# board1_328.net
KiCad netlist of a schematic drawn in EAGLE
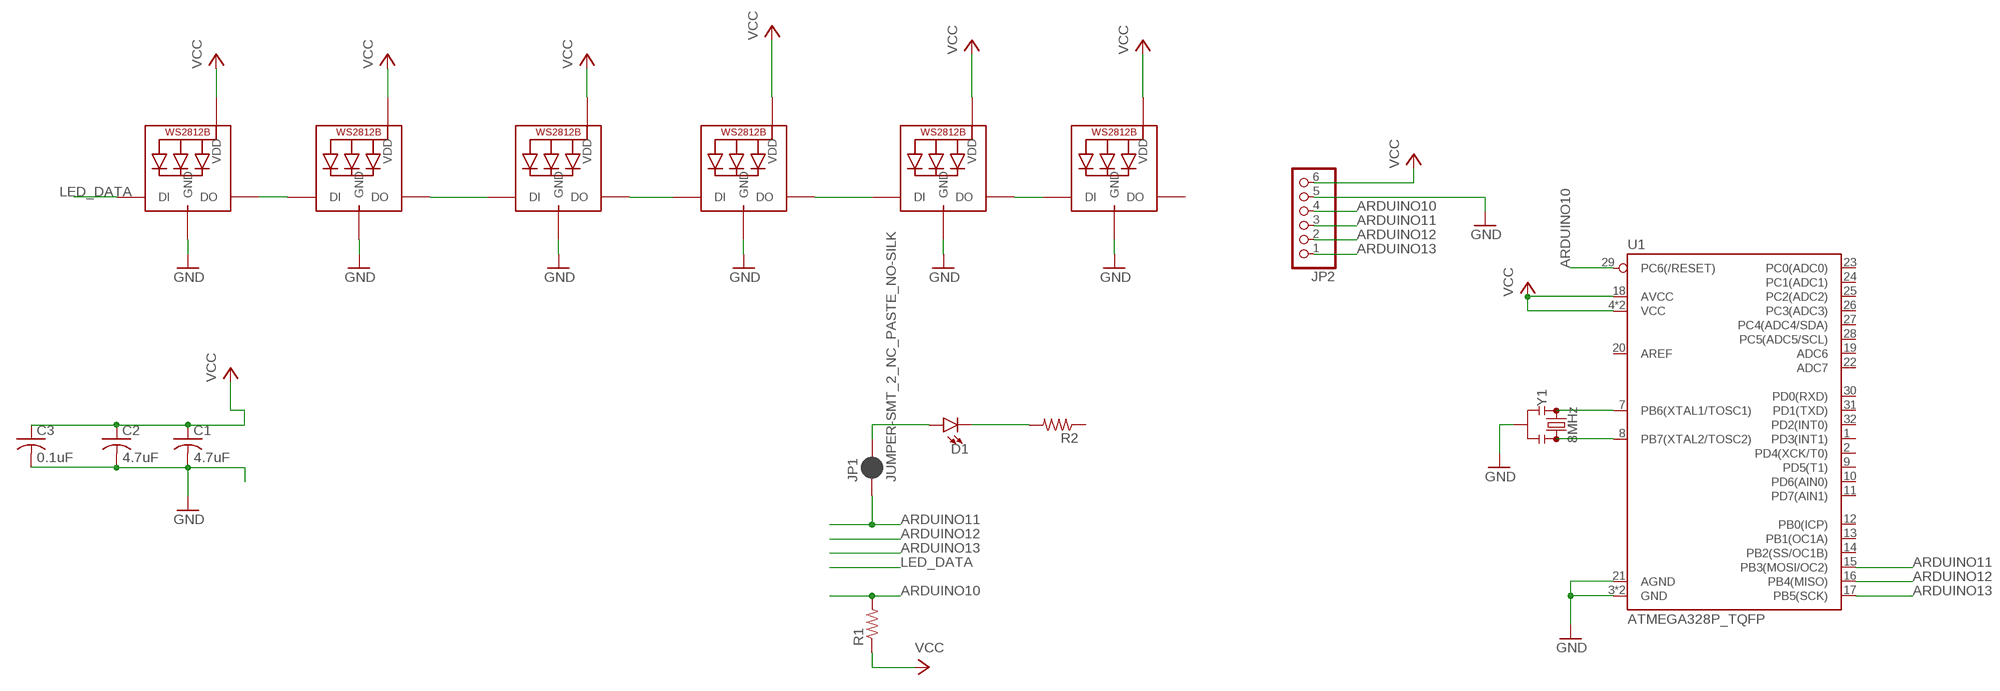
[diagram p0: schematic, sheet 1]

(export (version "E")
  (design (tool "Eeschema 10.0.6"))
  (components
    (comp (ref "C1")
      (value "4.7uF")
      (footprint "eagle-import:C0603")
      (libsource (lib "eagle-import") (part "C-USC0603"))
    )
    (comp (ref "C2")
      (value "4.7uF")
      (footprint "eagle-import:C0603")
      (libsource (lib "eagle-import") (part "C-USC0603"))
    )
    (comp (ref "C3")
      (value "0.1uF")
      (footprint "eagle-import:C0603")
      (libsource (lib "eagle-import") (part "C-USC0603"))
    )
    (comp (ref "D1")
      (value "LED0603")
      (footprint "eagle-import:LED-0603")
      (libsource (lib "eagle-import") (part "LED0603"))
    )
    (comp (ref "JP1")
      (value "JUMPER-SMT_2_NC_PASTE_NO-SILK")
      (footprint "eagle-import:SMT-JUMPER_2_NC_PASTE_NO-SILK")
      (libsource (lib "eagle-import") (part "JUMPER-SMT_2_NC_PASTE_NO-SILK"))
    )
    (comp (ref "JP2")
      (value "PINHD-1X6")
      (footprint "eagle-import:1X06")
      (libsource (lib "eagle-import") (part "PINHD-1X6"))
    )
    (comp (ref "LED1")
      (value "WS2812B5050")
      (footprint "eagle-import:WS2812B")
      (libsource (lib "eagle-import") (part "WS2812B5050"))
    )
    (comp (ref "LED2")
      (value "WS2812B5050")
      (footprint "eagle-import:WS2812B")
      (libsource (lib "eagle-import") (part "WS2812B5050"))
    )
    (comp (ref "LED3")
      (value "WS2812B5050")
      (footprint "eagle-import:WS2812B")
      (libsource (lib "eagle-import") (part "WS2812B5050"))
    )
    (comp (ref "LED4")
      (value "WS2812B5050")
      (footprint "eagle-import:WS2812B")
      (libsource (lib "eagle-import") (part "WS2812B5050"))
    )
    (comp (ref "LED5")
      (value "WS2812B5050")
      (footprint "eagle-import:WS2812B")
      (libsource (lib "eagle-import") (part "WS2812B5050"))
    )
    (comp (ref "LED6")
      (value "WS2812B5050")
      (footprint "eagle-import:WS2812B")
      (libsource (lib "eagle-import") (part "WS2812B5050"))
    )
    (comp (ref "R1")
      (value "R-US_R0603")
      (footprint "eagle-import:R0603")
      (libsource (lib "eagle-import") (part "R-US_R0603"))
    )
    (comp (ref "R2")
      (value "R-US_R0603")
      (footprint "eagle-import:R0603")
      (libsource (lib "eagle-import") (part "R-US_R0603"))
    )
    (comp (ref "U1")
      (value "ATMEGA328P_TQFP")
      (footprint "eagle-import:TQFP32-08")
      (libsource (lib "eagle-import") (part "ATMEGA328P_TQFP"))
    )
    (comp (ref "Y1")
      (value "8MHz")
      (footprint "eagle-import:RESONATOR-SMD-3.2X1.3")
      (libsource (lib "eagle-import") (part "RESONATOR-8MHZSMD_3.2X1.3"))
    )
  )
  (nets
    (net (code "1") (name "/ARDUINO10") (class "Default")
      (node (ref "JP2") (pin "4") (pinfunction "4_4") (pintype "passive"))
      (node (ref "R1") (pin "2") (pinfunction "2_2") (pintype "passive"))
      (node (ref "U1") (pin "29") (pinfunction "PC6(/RESET)_29") (pintype "bidirectional"))
    )
    (net (code "2") (name "/ARDUINO11") (class "Default")
      (node (ref "JP1") (pin "1") (pinfunction "1_1") (pintype "passive"))
      (node (ref "JP2") (pin "3") (pinfunction "3_3") (pintype "passive"))
      (node (ref "U1") (pin "15") (pinfunction "PB3(MOSI/OC2)_15") (pintype "bidirectional"))
    )
    (net (code "3") (name "/ARDUINO12") (class "Default")
      (node (ref "JP2") (pin "2") (pinfunction "2_2") (pintype "passive"))
      (node (ref "U1") (pin "16") (pinfunction "PB4(MISO)_16") (pintype "bidirectional"))
    )
    (net (code "4") (name "/ARDUINO13") (class "Default")
      (node (ref "JP2") (pin "1") (pinfunction "1_1") (pintype "passive"))
      (node (ref "U1") (pin "17") (pinfunction "PB5(SCK)_17") (pintype "bidirectional"))
    )
    (net (code "5") (name "/LED_DATA") (class "Default")
      (node (ref "LED1") (pin "4-DIN") (pinfunction "DI_4-DIN") (pintype "input"))
    )
    (net (code "6") (name "GND") (class "Default")
      (node (ref "C1") (pin "2") (pinfunction "2_2") (pintype "passive"))
      (node (ref "C2") (pin "2") (pinfunction "2_2") (pintype "passive"))
      (node (ref "C3") (pin "2") (pinfunction "2_2") (pintype "passive"))
      (node (ref "JP2") (pin "5") (pinfunction "5_5") (pintype "passive"))
      (node (ref "LED1") (pin "3-GND") (pinfunction "GND_3-GND") (pintype "power_in"))
      (node (ref "LED2") (pin "3-GND") (pinfunction "GND_3-GND") (pintype "power_in"))
      (node (ref "LED3") (pin "3-GND") (pinfunction "GND_3-GND") (pintype "power_in"))
      (node (ref "LED4") (pin "3-GND") (pinfunction "GND_3-GND") (pintype "power_in"))
      (node (ref "LED5") (pin "3-GND") (pinfunction "GND_3-GND") (pintype "power_in"))
      (node (ref "LED6") (pin "3-GND") (pinfunction "GND_3-GND") (pintype "power_in"))
      (node (ref "U1") (pin "21") (pinfunction "AGND_21") (pintype "bidirectional"))
      (node (ref "U1") (pin "3") (pinfunction "GND_3") (pintype "bidirectional"))
      (node (ref "U1") (pin "5") (pinfunction "GND_5") (pintype "bidirectional"))
      (node (ref "Y1") (pin "2") (pinfunction "2_2") (pintype "passive"))
    )
    (net (code "7") (name "Net-(D1-PadA)") (class "Default")
      (node (ref "D1") (pin "A") (pinfunction "A_A") (pintype "passive"))
      (node (ref "JP1") (pin "2") (pinfunction "2_2") (pintype "passive"))
    )
    (net (code "8") (name "Net-(D1-PadC)") (class "Default")
      (node (ref "D1") (pin "C") (pinfunction "C_C") (pintype "passive"))
      (node (ref "R2") (pin "2") (pinfunction "2_2") (pintype "passive"))
    )
    (net (code "9") (name "Net-(LED1-DO)") (class "Default")
      (node (ref "LED1") (pin "2-DOUT") (pinfunction "DO_2-DOUT") (pintype "output"))
      (node (ref "LED2") (pin "4-DIN") (pinfunction "DI_4-DIN") (pintype "input"))
    )
    (net (code "10") (name "Net-(LED2-DO)") (class "Default")
      (node (ref "LED2") (pin "2-DOUT") (pinfunction "DO_2-DOUT") (pintype "output"))
      (node (ref "LED3") (pin "4-DIN") (pinfunction "DI_4-DIN") (pintype "input"))
    )
    (net (code "11") (name "Net-(LED3-DO)") (class "Default")
      (node (ref "LED3") (pin "2-DOUT") (pinfunction "DO_2-DOUT") (pintype "output"))
      (node (ref "LED4") (pin "4-DIN") (pinfunction "DI_4-DIN") (pintype "input"))
    )
    (net (code "12") (name "Net-(LED4-DO)") (class "Default")
      (node (ref "LED4") (pin "2-DOUT") (pinfunction "DO_2-DOUT") (pintype "output"))
      (node (ref "LED5") (pin "4-DIN") (pinfunction "DI_4-DIN") (pintype "input"))
    )
    (net (code "13") (name "Net-(LED5-DO)") (class "Default")
      (node (ref "LED5") (pin "2-DOUT") (pinfunction "DO_2-DOUT") (pintype "output"))
      (node (ref "LED6") (pin "4-DIN") (pinfunction "DI_4-DIN") (pintype "input"))
    )
    (net (code "14") (name "Net-(U1-PB6(XTAL1{slash}TOSC1))") (class "Default")
      (node (ref "U1") (pin "7") (pinfunction "PB6(XTAL1/TOSC1)_7") (pintype "bidirectional"))
      (node (ref "Y1") (pin "1") (pinfunction "1_1") (pintype "passive"))
    )
    (net (code "15") (name "Net-(U1-PB7(XTAL2{slash}TOSC2))") (class "Default")
      (node (ref "U1") (pin "8") (pinfunction "PB7(XTAL2/TOSC2)_8") (pintype "bidirectional"))
      (node (ref "Y1") (pin "3") (pinfunction "3_3") (pintype "passive"))
    )
    (net (code "16") (name "VCC") (class "Default")
      (node (ref "C1") (pin "1") (pinfunction "1_1") (pintype "passive"))
      (node (ref "C2") (pin "1") (pinfunction "1_1") (pintype "passive"))
      (node (ref "C3") (pin "1") (pinfunction "1_1") (pintype "passive"))
      (node (ref "JP2") (pin "6") (pinfunction "6_6") (pintype "passive"))
      (node (ref "LED1") (pin "1-VDD") (pinfunction "VDD_1-VDD") (pintype "power_in"))
      (node (ref "LED2") (pin "1-VDD") (pinfunction "VDD_1-VDD") (pintype "power_in"))
      (node (ref "LED3") (pin "1-VDD") (pinfunction "VDD_1-VDD") (pintype "power_in"))
      (node (ref "LED4") (pin "1-VDD") (pinfunction "VDD_1-VDD") (pintype "power_in"))
      (node (ref "LED5") (pin "1-VDD") (pinfunction "VDD_1-VDD") (pintype "power_in"))
      (node (ref "LED6") (pin "1-VDD") (pinfunction "VDD_1-VDD") (pintype "power_in"))
      (node (ref "R1") (pin "1") (pinfunction "1_1") (pintype "passive"))
      (node (ref "U1") (pin "18") (pinfunction "AVCC_18") (pintype "bidirectional"))
      (node (ref "U1") (pin "4") (pinfunction "VCC_4") (pintype "bidirectional"))
      (node (ref "U1") (pin "6") (pinfunction "VCC_6") (pintype "bidirectional"))
    )
    (net (code "17") (name "unconnected-(LED6-DO-Pad2-DOUT)") (class "Default")
      (node (ref "LED6") (pin "2-DOUT") (pinfunction "DO_2-DOUT") (pintype "output"))
    )
    (net (code "18") (name "unconnected-(R2-Pad1)") (class "Default")
      (node (ref "R2") (pin "1") (pinfunction "1_1") (pintype "passive"))
    )
    (net (code "19") (name "unconnected-(U1-ADC6-Pad19)") (class "Default")
      (node (ref "U1") (pin "19") (pinfunction "ADC6_19") (pintype "bidirectional"))
    )
    (net (code "20") (name "unconnected-(U1-ADC7-Pad22)") (class "Default")
      (node (ref "U1") (pin "22") (pinfunction "ADC7_22") (pintype "bidirectional"))
    )
    (net (code "21") (name "unconnected-(U1-AREF-Pad20)") (class "Default")
      (node (ref "U1") (pin "20") (pinfunction "AREF_20") (pintype "bidirectional"))
    )
    (net (code "22") (name "unconnected-(U1-PB0(ICP)-Pad12)") (class "Default")
      (node (ref "U1") (pin "12") (pinfunction "PB0(ICP)_12") (pintype "bidirectional"))
    )
    (net (code "23") (name "unconnected-(U1-PB1(OC1A)-Pad13)") (class "Default")
      (node (ref "U1") (pin "13") (pinfunction "PB1(OC1A)_13") (pintype "bidirectional"))
    )
    (net (code "24") (name "unconnected-(U1-PB2(SS{slash}OC1B)-Pad14)") (class "Default")
      (node (ref "U1") (pin "14") (pinfunction "PB2(SS/OC1B)_14") (pintype "bidirectional"))
    )
    (net (code "25") (name "unconnected-(U1-PC0(ADC0)-Pad23)") (class "Default")
      (node (ref "U1") (pin "23") (pinfunction "PC0(ADC0)_23") (pintype "bidirectional"))
    )
    (net (code "26") (name "unconnected-(U1-PC1(ADC1)-Pad24)") (class "Default")
      (node (ref "U1") (pin "24") (pinfunction "PC1(ADC1)_24") (pintype "bidirectional"))
    )
    (net (code "27") (name "unconnected-(U1-PC2(ADC2)-Pad25)") (class "Default")
      (node (ref "U1") (pin "25") (pinfunction "PC2(ADC2)_25") (pintype "bidirectional"))
    )
    (net (code "28") (name "unconnected-(U1-PC3(ADC3)-Pad26)") (class "Default")
      (node (ref "U1") (pin "26") (pinfunction "PC3(ADC3)_26") (pintype "bidirectional"))
    )
    (net (code "29") (name "unconnected-(U1-PC4(ADC4{slash}SDA)-Pad27)") (class "Default")
      (node (ref "U1") (pin "27") (pinfunction "PC4(ADC4/SDA)_27") (pintype "bidirectional"))
    )
    (net (code "30") (name "unconnected-(U1-PC5(ADC5{slash}SCL)-Pad28)") (class "Default")
      (node (ref "U1") (pin "28") (pinfunction "PC5(ADC5/SCL)_28") (pintype "bidirectional"))
    )
    (net (code "31") (name "unconnected-(U1-PD0(RXD)-Pad30)") (class "Default")
      (node (ref "U1") (pin "30") (pinfunction "PD0(RXD)_30") (pintype "bidirectional"))
    )
    (net (code "32") (name "unconnected-(U1-PD1(TXD)-Pad31)") (class "Default")
      (node (ref "U1") (pin "31") (pinfunction "PD1(TXD)_31") (pintype "bidirectional"))
    )
    (net (code "33") (name "unconnected-(U1-PD2(INT0)-Pad32)") (class "Default")
      (node (ref "U1") (pin "32") (pinfunction "PD2(INT0)_32") (pintype "bidirectional"))
    )
    (net (code "34") (name "unconnected-(U1-PD3(INT1)-Pad1)") (class "Default")
      (node (ref "U1") (pin "1") (pinfunction "PD3(INT1)_1") (pintype "bidirectional"))
    )
    (net (code "35") (name "unconnected-(U1-PD4(XCK{slash}T0)-Pad2)") (class "Default")
      (node (ref "U1") (pin "2") (pinfunction "PD4(XCK/T0)_2") (pintype "bidirectional"))
    )
    (net (code "36") (name "unconnected-(U1-PD5(T1)-Pad9)") (class "Default")
      (node (ref "U1") (pin "9") (pinfunction "PD5(T1)_9") (pintype "bidirectional"))
    )
    (net (code "37") (name "unconnected-(U1-PD6(AIN0)-Pad10)") (class "Default")
      (node (ref "U1") (pin "10") (pinfunction "PD6(AIN0)_10") (pintype "bidirectional"))
    )
    (net (code "38") (name "unconnected-(U1-PD7(AIN1)-Pad11)") (class "Default")
      (node (ref "U1") (pin "11") (pinfunction "PD7(AIN1)_11") (pintype "bidirectional"))
    )
  )
)
